# 07_POWER.net
KiCad netlist of a schematic drawn in Altium Designer
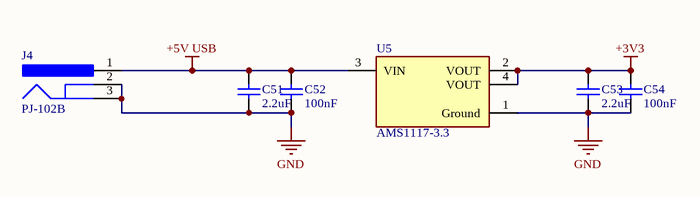
[diagram p0: 07. POWER.SchDoc]

(export (version "E")
  (design (tool "Eeschema 10.0.6"))
  (components
    (comp (ref "C51")
      (value "2.2uF")
      (footprint "CAPC1608X90X35NL10T15")
      (fields (field (name "MANUFACTURER") "Murata") (field (name "PART NUMBER") "GCM188R70J225KE22D"))
      (libsource (lib "Altium Content Vault") (part "CAP"))
    )
    (comp (ref "C52")
      (value "100nF")
      (footprint "CAPC1005X56X25NL10T15")
      (fields
        (field (name "MANUFACTURER") "AVX Interconnect / Elco")
        (field (name "PART NUMBER") "04026D104KAT2A")
      )
      (libsource (lib "Altium Content Vault") (part "CAP"))
    )
    (comp (ref "C53")
      (value "2.2uF")
      (footprint "CAPC1608X90X35NL10T15")
      (fields (field (name "MANUFACTURER") "Murata") (field (name "PART NUMBER") "GCM188R70J225KE22D"))
      (libsource (lib "Altium Content Vault") (part "CAP"))
    )
    (comp (ref "C54")
      (value "100nF")
      (footprint "CAPC1005X56X25NL10T15")
      (fields
        (field (name "MANUFACTURER") "AVX Interconnect / Elco")
        (field (name "PART NUMBER") "04026D104KAT2A")
      )
      (libsource (lib "Altium Content Vault") (part "CAP"))
    )
    (comp (ref "J4")
      (value "PJ-102B")
      (footprint "CUI-PJ-102B_V")
      (fields (field (name "MANUFACTURER") "CUIInc."))
      (libsource (lib "Altium Content Vault") (part "JACK-2CD3-RN"))
    )
    (comp (ref "U5")
      (value "AMS1117-3.3")
      (footprint "FP-AMS1117-IPC_B")
      (description "LDO Voltage Regulators 1A, 3.3V")
      (fields
        (field (name "OCTOPART") "https://octopart.com/ams1117-3.3-advanced+monolithic+systems-25899300")
        (field (name "MANUFACTURER") "Advanced Monolithic Systems")
      )
      (libsource (lib "Altium Content Vault") (part "8bdbb5f8e77002000e30dd2845d0354"))
    )
  )
  (nets
    (net (code "1") (name "+3V3") (class "Default")
      (node (ref "C53") (pin "2") (pinfunction "2_2") (pintype "passive"))
      (node (ref "C54") (pin "2") (pinfunction "2_2") (pintype "passive"))
      (node (ref "U5") (pin "2") (pinfunction "VOUT_2") (pintype "passive"))
      (node (ref "U5") (pin "4") (pinfunction "VOUT_4") (pintype "passive"))
    )
    (net (code "2") (name "+5V USB") (class "Default")
      (node (ref "C51") (pin "2") (pinfunction "2_2") (pintype "passive"))
      (node (ref "C52") (pin "2") (pinfunction "2_2") (pintype "passive"))
      (node (ref "J4") (pin "1") (pinfunction "1_1") (pintype "passive"))
      (node (ref "U5") (pin "3") (pinfunction "VIN_3") (pintype "power_in"))
    )
    (net (code "3") (name "GND") (class "Default")
      (node (ref "C51") (pin "1") (pinfunction "1_1") (pintype "passive"))
      (node (ref "C52") (pin "1") (pinfunction "1_1") (pintype "passive"))
      (node (ref "C53") (pin "1") (pinfunction "1_1") (pintype "passive"))
      (node (ref "C54") (pin "1") (pinfunction "1_1") (pintype "passive"))
      (node (ref "J4") (pin "2") (pinfunction "2_2") (pintype "passive"))
      (node (ref "J4") (pin "3") (pinfunction "3_3") (pintype "passive"))
      (node (ref "U5") (pin "1") (pinfunction "Ground_1") (pintype "power_in"))
    )
  )
)
